# Audio.net
KiCad netlist of a schematic drawn in Altium Designer
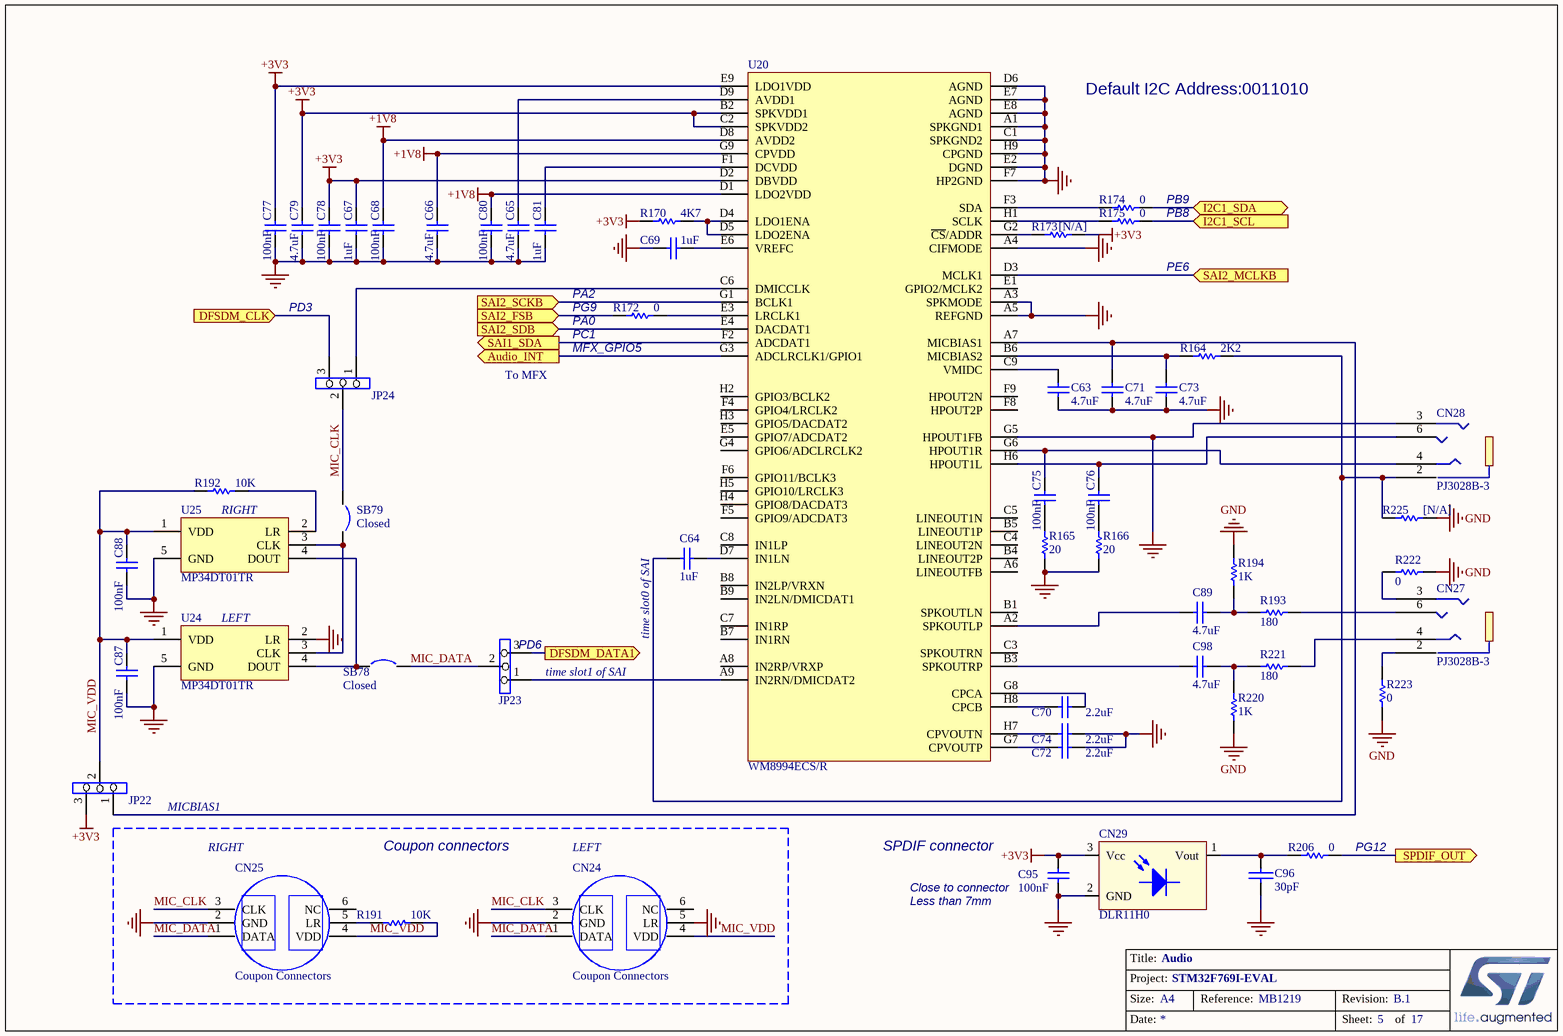
[diagram p0: Audio.SchDoc]

(export (version "E")
  (design (tool "Eeschema 10.0.6"))
  (components
    (comp (ref "C63")
      (value "4.7uF")
      (footprint "0603C")
      (description "Capacitor")
      (fields (field (name "PUBLISHER") "Altium Limited"))
      (libsource (lib "Miscellaneous Devices") (part "Cap"))
    )
    (comp (ref "C64")
      (value "1uF")
      (footprint "0603C")
      (description "Capacitor")
      (fields (field (name "PUBLISHER") "Altium Limited"))
      (libsource (lib "Miscellaneous Devices") (part "CAP"))
    )
    (comp (ref "C65")
      (value "4.7uF")
      (footprint "0603C")
      (description "Capacitor")
      (fields (field (name "PUBLISHER") "Altium Limited"))
      (libsource (lib "Miscellaneous Devices") (part "Cap"))
    )
    (comp (ref "C66")
      (value "4.7uF")
      (footprint "0603C")
      (description "Capacitor")
      (fields (field (name "PUBLISHER") "Altium Limited"))
      (libsource (lib "Miscellaneous Devices") (part "Cap"))
    )
    (comp (ref "C67")
      (value "1uF")
      (footprint "0603C")
      (description "Capacitor")
      (fields (field (name "PUBLISHER") "Altium Limited"))
      (libsource (lib "Miscellaneous Devices") (part "CAP"))
    )
    (comp (ref "C68")
      (value "100nF")
      (footprint "0603C")
      (description "Capacitor")
      (fields (field (name "PUBLISHER") "Altium Limited"))
      (libsource (lib "Miscellaneous Devices") (part "Cap"))
    )
    (comp (ref "C69")
      (value "1uF")
      (footprint "0603C")
      (description "Capacitor")
      (fields (field (name "PUBLISHER") "Altium Limited"))
      (libsource (lib "Miscellaneous Devices") (part "CAP"))
    )
    (comp (ref "C70")
      (value "2.2uF")
      (footprint "0603C")
      (description "Capacitor")
      (fields (field (name "PUBLISHER") "Altium Limited"))
      (libsource (lib "Miscellaneous Devices") (part "CAP"))
    )
    (comp (ref "C71")
      (value "4.7uF")
      (footprint "0603C")
      (description "Capacitor")
      (fields (field (name "PUBLISHER") "Altium Limited"))
      (libsource (lib "Miscellaneous Devices") (part "Cap"))
    )
    (comp (ref "C72")
      (value "2.2uF")
      (footprint "0603C")
      (description "Capacitor")
      (fields (field (name "PUBLISHER") "Altium Limited"))
      (libsource (lib "Miscellaneous Devices") (part "CAP"))
    )
    (comp (ref "C73")
      (value "4.7uF")
      (footprint "0603C")
      (description "Capacitor")
      (fields (field (name "PUBLISHER") "Altium Limited"))
      (libsource (lib "Miscellaneous Devices") (part "Cap"))
    )
    (comp (ref "C74")
      (value "2.2uF")
      (footprint "0603C")
      (description "Capacitor")
      (fields (field (name "PUBLISHER") "Altium Limited"))
      (libsource (lib "Miscellaneous Devices") (part "CAP"))
    )
    (comp (ref "C75")
      (value "100nF")
      (footprint "0603C")
      (description "Capacitor")
      (fields (field (name "PUBLISHER") "Altium Limited"))
      (libsource (lib "Miscellaneous Devices") (part "Cap"))
    )
    (comp (ref "C76")
      (value "100nF")
      (footprint "0603C")
      (description "Capacitor")
      (fields (field (name "PUBLISHER") "Altium Limited"))
      (libsource (lib "Miscellaneous Devices") (part "Cap"))
    )
    (comp (ref "C77")
      (value "100nF")
      (footprint "0603C")
      (description "Capacitor")
      (fields (field (name "PUBLISHER") "Altium Limited"))
      (libsource (lib "Miscellaneous Devices") (part "Cap"))
    )
    (comp (ref "C78")
      (value "100nF")
      (footprint "0603C")
      (description "Capacitor")
      (fields (field (name "PUBLISHER") "Altium Limited"))
      (libsource (lib "Miscellaneous Devices") (part "Cap"))
    )
    (comp (ref "C79")
      (value "4.7uF")
      (footprint "0603C")
      (description "Capacitor")
      (fields (field (name "PUBLISHER") "Altium Limited"))
      (libsource (lib "Miscellaneous Devices") (part "Cap"))
    )
    (comp (ref "C80")
      (value "100nF")
      (footprint "0603C")
      (description "Capacitor")
      (fields (field (name "PUBLISHER") "Altium Limited"))
      (libsource (lib "Miscellaneous Devices") (part "Cap"))
    )
    (comp (ref "C81")
      (value "1uF")
      (footprint "0603C")
      (description "Capacitor")
      (fields (field (name "PUBLISHER") "Altium Limited"))
      (libsource (lib "Miscellaneous Devices") (part "CAP"))
    )
    (comp (ref "C87")
      (value "100nF")
      (footprint "0603C")
      (description "Capacitor")
      (fields (field (name "PUBLISHER") "Altium Limited"))
      (libsource (lib "Miscellaneous Devices") (part "Cap"))
    )
    (comp (ref "C88")
      (value "100nF")
      (footprint "0603C")
      (description "Capacitor")
      (fields (field (name "PUBLISHER") "Altium Limited"))
      (libsource (lib "Miscellaneous Devices") (part "Cap"))
    )
    (comp (ref "C89")
      (value "4.7uF")
      (footprint "0603C")
      (description "Capacitor")
      (fields (field (name "PUBLISHER") "Altium Limited"))
      (libsource (lib "Miscellaneous Devices") (part "Cap"))
    )
    (comp (ref "C95")
      (value "100nF")
      (footprint "0603C")
      (description "Capacitor")
      (fields (field (name "PUBLISHER") "Altium Limited"))
      (libsource (lib "Miscellaneous Devices") (part "Cap"))
    )
    (comp (ref "C96")
      (value "30pF")
      (footprint "0603C")
      (description "Capacitor")
      (libsource (lib "*") (part "CAP"))
    )
    (comp (ref "C98")
      (value "4.7uF")
      (footprint "0603C")
      (description "Capacitor")
      (fields (field (name "PUBLISHER") "Altium Limited"))
      (libsource (lib "Miscellaneous Devices") (part "Cap"))
    )
    (comp (ref "CN24")
      (value "Coupon Connectors")
      (footprint "Coupon")
      (description "Header, 3-Pin, Single row")
      (fields (field (name "PUBLISHER") "Altium Limited"))
      (libsource (lib "MB1167") (part "Coupon Connectors"))
    )
    (comp (ref "CN25")
      (value "Coupon Connectors")
      (footprint "Coupon")
      (description "Header, 3-Pin, Single row")
      (fields (field (name "PUBLISHER") "Altium Limited"))
      (libsource (lib "MB1167") (part "Coupon Connectors"))
    )
    (comp (ref "CN27") (value "PJ3028B-3") (footprint "PJ3028B") (libsource (lib "MB786") (part "PJ3028B-3")))
    (comp (ref "CN28") (value "PJ3028B-3") (footprint "PJ3028B") (libsource (lib "MB786") (part "PJ3028B-3")))
    (comp (ref "CN29")
      (value "DLR11H0")
      (footprint "CONN_DLR11H0")
      (libsource (lib "MB1167_1") (part "OPTO"))
    )
    (comp (ref "JP22") (value "~") (footprint "SIP3") (libsource (lib "STR910_SCHLIB") (part "Jumper3")))
    (comp (ref "JP23") (value "~") (footprint "SIP3") (libsource (lib "STR910_SCHLIB") (part "Jumper3")))
    (comp (ref "JP24") (value "~") (footprint "SIP3") (libsource (lib "STR910_SCHLIB") (part "Jumper3")))
    (comp (ref "R164")
      (value "2K2")
      (footprint "0603R")
      (description "Resistor")
      (fields (field (name "PUBLISHER") "Altium Limited"))
      (libsource (lib "Miscellaneous Devices") (part "Res1"))
    )
    (comp (ref "R165")
      (value "20")
      (footprint "0603R")
      (description "Resistor")
      (fields (field (name "PUBLISHER") "Altium Limited"))
      (libsource (lib "Miscellaneous Devices") (part "Res1"))
    )
    (comp (ref "R166")
      (value "20")
      (footprint "0603R")
      (description "Resistor")
      (fields (field (name "PUBLISHER") "Altium Limited"))
      (libsource (lib "Miscellaneous Devices") (part "Res1"))
    )
    (comp (ref "R170")
      (value "4K7")
      (footprint "0603R")
      (description "Resistor")
      (fields (field (name "PUBLISHER") "Altium Limited"))
      (libsource (lib "Miscellaneous Devices") (part "Res1"))
    )
    (comp (ref "R172")
      (value "0")
      (footprint "0603R")
      (description "Resistor")
      (fields (field (name "PUBLISHER") "Altium Limited"))
      (libsource (lib "Miscellaneous Devices") (part "Res1"))
    )
    (comp (ref "R173")
      (value "[N/A]")
      (footprint "0603R")
      (description "Resistor")
      (fields (field (name "PUBLISHER") "Altium Limited"))
      (libsource (lib "Miscellaneous Devices") (part "Res1"))
    )
    (comp (ref "R174")
      (value "0")
      (footprint "0603R")
      (description "Resistor")
      (fields (field (name "PUBLISHER") "Altium Limited"))
      (libsource (lib "Miscellaneous Devices") (part "Res1"))
    )
    (comp (ref "R175")
      (value "0")
      (footprint "0603R")
      (description "Resistor")
      (fields (field (name "PUBLISHER") "Altium Limited"))
      (libsource (lib "Miscellaneous Devices") (part "Res1"))
    )
    (comp (ref "R191")
      (value "10K")
      (footprint "0603R")
      (description "Resistor")
      (fields (field (name "PUBLISHER") "Altium Limited"))
      (libsource (lib "Miscellaneous Devices") (part "Res1"))
    )
    (comp (ref "R192")
      (value "10K")
      (footprint "0603R")
      (description "Resistor")
      (fields (field (name "PUBLISHER") "Altium Limited"))
      (libsource (lib "Miscellaneous Devices") (part "Res1"))
    )
    (comp (ref "R193")
      (value "180")
      (footprint "0402R")
      (description "Resistor")
      (fields (field (name "PUBLISHER") "Altium Limited"))
      (libsource (lib "Miscellaneous Devices") (part "Res1"))
    )
    (comp (ref "R194")
      (value "1K")
      (footprint "0402R")
      (description "Resistor")
      (fields (field (name "PUBLISHER") "Altium Limited"))
      (libsource (lib "Miscellaneous Devices") (part "Res1"))
    )
    (comp (ref "R206")
      (value "0")
      (footprint "0603R")
      (description "Resistor")
      (fields (field (name "PUBLISHER") "Altium Limited"))
      (libsource (lib "Miscellaneous Devices") (part "Res1"))
    )
    (comp (ref "R220")
      (value "1K")
      (footprint "0402R")
      (description "Resistor")
      (fields (field (name "PUBLISHER") "Altium Limited"))
      (libsource (lib "Miscellaneous Devices") (part "Res1"))
    )
    (comp (ref "R221")
      (value "180")
      (footprint "0402R")
      (description "Resistor")
      (fields (field (name "PUBLISHER") "Altium Limited"))
      (libsource (lib "Miscellaneous Devices") (part "Res1"))
    )
    (comp (ref "R222")
      (value "0")
      (footprint "0603R")
      (description "Resistor")
      (fields (field (name "PUBLISHER") "Altium Limited"))
      (libsource (lib "Miscellaneous Devices") (part "Res1"))
    )
    (comp (ref "R223")
      (value "0")
      (footprint "0603R")
      (description "Resistor")
      (fields (field (name "PUBLISHER") "Altium Limited"))
      (libsource (lib "Miscellaneous Devices") (part "Res1"))
    )
    (comp (ref "R225")
      (value "[N/A]")
      (footprint "0603R")
      (description "Resistor")
      (fields (field (name "PUBLISHER") "Altium Limited"))
      (libsource (lib "Miscellaneous Devices") (part "Res1"))
    )
    (comp (ref "SB78")
      (value "Closed")
      (footprint "SB_0603")
      (description "Circuit Breaker")
      (fields (field (name "PUBLISHER") "Altium Limited"))
      (libsource (lib "MB1167") (part "Circuit Breaker_close"))
    )
    (comp (ref "SB79")
      (value "Closed")
      (footprint "SB_0603")
      (description "Circuit Breaker")
      (fields (field (name "PUBLISHER") "Altium Limited"))
      (libsource (lib "MB1167") (part "Circuit Breaker_close"))
    )
    (comp (ref "U20")
      (value "WM8994ECS/R")
      (footprint "BGA72_0R5_4R5X4")
      (libsource (lib "mb1045") (part "WM8994ECS/R"))
    )
    (comp (ref "U24")
      (value "MP34DT01TR")
      (footprint "MP34DT01TR")
      (description "MEMS audio sensor")
      (fields (field (name "PUBLISHER") "Altium Limited"))
      (libsource (lib "mb1045") (part "MP34DT01TR"))
    )
    (comp (ref "U25")
      (value "MP34DT01TR")
      (footprint "MP34DT01TR")
      (description "MEMS audio sensor")
      (fields (field (name "PUBLISHER") "Altium Limited"))
      (libsource (lib "mb1045") (part "MP34DT01TR"))
    )
  )
  (nets
    (net (code "1") (name "+1V8") (class "Default")
      (node (ref "C66") (pin "1") (pinfunction "1_1") (pintype "passive"))
      (node (ref "C68") (pin "1") (pinfunction "1_1") (pintype "passive"))
      (node (ref "C80") (pin "1") (pinfunction "1_1") (pintype "passive"))
      (node (ref "U20") (pin "D1") (pinfunction "LDO2VDD_D1") (pintype "passive"))
      (node (ref "U20") (pin "D8") (pinfunction "AVDD2_D8") (pintype "passive"))
      (node (ref "U20") (pin "G9") (pinfunction "CPVDD_G9") (pintype "passive"))
    )
    (net (code "2") (name "+3V3") (class "Default")
      (node (ref "C67") (pin "1") (pinfunction "1_1") (pintype "passive"))
      (node (ref "C77") (pin "1") (pinfunction "1_1") (pintype "passive"))
      (node (ref "C78") (pin "1") (pinfunction "1_1") (pintype "passive"))
      (node (ref "C79") (pin "1") (pinfunction "1_1") (pintype "passive"))
      (node (ref "C95") (pin "2") (pinfunction "2_2") (pintype "passive"))
      (node (ref "CN29") (pin "3") (pinfunction "Vcc_3") (pintype "passive"))
      (node (ref "JP22") (pin "3") (pintype "passive"))
      (node (ref "R170") (pin "2") (pinfunction "2_2") (pintype "passive"))
      (node (ref "R173") (pin "1") (pinfunction "1_1") (pintype "passive"))
      (node (ref "U20") (pin "B2") (pinfunction "SPKVDD1_B2") (pintype "passive"))
      (node (ref "U20") (pin "C2") (pinfunction "SPKVDD2_C2") (pintype "passive"))
      (node (ref "U20") (pin "D2") (pinfunction "DBVDD_D2") (pintype "passive"))
      (node (ref "U20") (pin "E9") (pinfunction "LDO1VDD_E9") (pintype "passive"))
    )
    (net (code "3") (name "/Audio_INT") (class "Default")
      (node (ref "U20") (pin "G3") (pinfunction "ADCLRCLK1/GPIO1_G3") (pintype "passive"))
    )
    (net (code "4") (name "/DFSDM_CLK") (class "Default") (node (ref "JP24") (pin "3") (pintype "passive")))
    (net (code "5") (name "/DFSDM_DATA1") (class "Default") (node (ref "JP23") (pin "3") (pintype "passive")))
    (net (code "6") (name "/I2C1_SCL") (class "Default")
      (node (ref "R175") (pin "1") (pinfunction "1_1") (pintype "passive"))
    )
    (net (code "7") (name "/I2C1_SDA") (class "Default")
      (node (ref "R174") (pin "1") (pinfunction "1_1") (pintype "passive"))
    )
    (net (code "8") (name "/MIC_CLK") (class "Default")
      (node (ref "CN24") (pin "3") (pinfunction "CLK_3") (pintype "passive"))
      (node (ref "CN25") (pin "3") (pinfunction "CLK_3") (pintype "passive"))
      (node (ref "JP24") (pin "2") (pintype "passive"))
      (node (ref "SB79") (pin "1") (pinfunction "1_1") (pintype "passive"))
    )
    (net (code "9") (name "/MIC_DATA") (class "Default")
      (node (ref "CN24") (pin "1") (pinfunction "DATA_1") (pintype "passive"))
      (node (ref "CN25") (pin "1") (pinfunction "DATA_1") (pintype "passive"))
      (node (ref "JP23") (pin "2") (pintype "passive"))
      (node (ref "SB78") (pin "2") (pinfunction "2_2") (pintype "passive"))
    )
    (net (code "10") (name "/MIC_VDD") (class "Default")
      (node (ref "C87") (pin "1") (pinfunction "1_1") (pintype "passive"))
      (node (ref "C88") (pin "1") (pinfunction "1_1") (pintype "passive"))
      (node (ref "CN24") (pin "4") (pinfunction "VDD_4") (pintype "passive"))
      (node (ref "CN25") (pin "4") (pinfunction "VDD_4") (pintype "passive"))
      (node (ref "JP22") (pin "2") (pintype "passive"))
      (node (ref "R191") (pin "2") (pinfunction "2_2") (pintype "passive"))
      (node (ref "R192") (pin "2") (pinfunction "2_2") (pintype "passive"))
      (node (ref "U24") (pin "1") (pinfunction "VDD_1") (pintype "passive"))
      (node (ref "U25") (pin "1") (pinfunction "VDD_1") (pintype "passive"))
    )
    (net (code "11") (name "/SAI1_SDA") (class "Default")
      (node (ref "U20") (pin "F2") (pinfunction "ADCDAT1_F2") (pintype "passive"))
    )
    (net (code "12") (name "/SAI2_FSB") (class "Default")
      (node (ref "R172") (pin "2") (pinfunction "2_2") (pintype "passive"))
    )
    (net (code "13") (name "/SAI2_MCLKB") (class "Default")
      (node (ref "U20") (pin "D3") (pinfunction "MCLK1_D3") (pintype "passive"))
    )
    (net (code "14") (name "/SAI2_SCKB") (class "Default")
      (node (ref "U20") (pin "G1") (pinfunction "BCLK1_G1") (pintype "passive"))
    )
    (net (code "15") (name "/SAI2_SDB") (class "Default")
      (node (ref "U20") (pin "E4") (pinfunction "DACDAT1_E4") (pintype "passive"))
    )
    (net (code "16") (name "/SPDIF_OUT") (class "Default")
      (node (ref "R206") (pin "1") (pinfunction "1_1") (pintype "passive"))
    )
    (net (code "17") (name "GND") (class "Default")
      (node (ref "C63") (pin "1") (pinfunction "1_1") (pintype "passive"))
      (node (ref "C65") (pin "2") (pinfunction "2_2") (pintype "passive"))
      (node (ref "C66") (pin "2") (pinfunction "2_2") (pintype "passive"))
      (node (ref "C67") (pin "2") (pinfunction "2_2") (pintype "passive"))
      (node (ref "C68") (pin "2") (pinfunction "2_2") (pintype "passive"))
      (node (ref "C69") (pin "2") (pinfunction "2_2") (pintype "passive"))
      (node (ref "C71") (pin "1") (pinfunction "1_1") (pintype "passive"))
      (node (ref "C72") (pin "2") (pinfunction "2_2") (pintype "passive"))
      (node (ref "C73") (pin "1") (pinfunction "1_1") (pintype "passive"))
      (node (ref "C74") (pin "2") (pinfunction "2_2") (pintype "passive"))
      (node (ref "C77") (pin "2") (pinfunction "2_2") (pintype "passive"))
      (node (ref "C78") (pin "2") (pinfunction "2_2") (pintype "passive"))
      (node (ref "C79") (pin "2") (pinfunction "2_2") (pintype "passive"))
      (node (ref "C80") (pin "2") (pinfunction "2_2") (pintype "passive"))
      (node (ref "C81") (pin "2") (pinfunction "2_2") (pintype "passive"))
      (node (ref "C87") (pin "2") (pinfunction "2_2") (pintype "passive"))
      (node (ref "C88") (pin "2") (pinfunction "2_2") (pintype "passive"))
      (node (ref "C95") (pin "1") (pinfunction "1_1") (pintype "passive"))
      (node (ref "C96") (pin "2") (pinfunction "2_2") (pintype "passive"))
      (node (ref "CN24") (pin "2") (pinfunction "GND_2") (pintype "passive"))
      (node (ref "CN24") (pin "5") (pinfunction "LR_5") (pintype "passive"))
      (node (ref "CN25") (pin "2") (pinfunction "GND_2") (pintype "passive"))
      (node (ref "CN28") (pin "3") (pintype "passive"))
      (node (ref "CN29") (pin "2") (pinfunction "GND_2") (pintype "passive"))
      (node (ref "R165") (pin "2") (pinfunction "2_2") (pintype "passive"))
      (node (ref "R166") (pin "2") (pinfunction "2_2") (pintype "passive"))
      (node (ref "R194") (pin "2") (pinfunction "2_2") (pintype "passive"))
      (node (ref "R220") (pin "1") (pinfunction "1_1") (pintype "passive"))
      (node (ref "R222") (pin "2") (pinfunction "2_2") (pintype "passive"))
      (node (ref "R223") (pin "2") (pinfunction "2_2") (pintype "passive"))
      (node (ref "R225") (pin "1") (pinfunction "1_1") (pintype "passive"))
      (node (ref "U20") (pin "A1") (pinfunction "SPKGND1_A1") (pintype "passive"))
      (node (ref "U20") (pin "A3") (pinfunction "SPKMODE_A3") (pintype "passive"))
      (node (ref "U20") (pin "A4") (pinfunction "CIFMODE_A4") (pintype "passive"))
      (node (ref "U20") (pin "A5") (pinfunction "REFGND_A5") (pintype "passive"))
      (node (ref "U20") (pin "C1") (pinfunction "SPKGND2_C1") (pintype "passive"))
      (node (ref "U20") (pin "D6") (pinfunction "AGND_D6") (pintype "passive"))
      (node (ref "U20") (pin "E2") (pinfunction "DGND_E2") (pintype "passive"))
      (node (ref "U20") (pin "E7") (pinfunction "AGND_E7") (pintype "passive"))
      (node (ref "U20") (pin "E8") (pinfunction "AGND_E8") (pintype "passive"))
      (node (ref "U20") (pin "F7") (pinfunction "HP2GND_F7") (pintype "passive"))
      (node (ref "U20") (pin "G5") (pinfunction "HPOUT1FB_G5") (pintype "passive"))
      (node (ref "U20") (pin "H9") (pinfunction "CPGND_H9") (pintype "passive"))
      (node (ref "U24") (pin "2") (pinfunction "LR_2") (pintype "passive"))
      (node (ref "U24") (pin "5") (pinfunction "GND_5") (pintype "passive"))
      (node (ref "U25") (pin "5") (pinfunction "GND_5") (pintype "passive"))
    )
    (net (code "18") (name "Net-(C64-Pad2)") (class "Default")
      (node (ref "C64") (pin "2") (pinfunction "2_2") (pintype "passive"))
      (node (ref "CN28") (pin "2") (pintype "passive"))
      (node (ref "R164") (pin "1") (pinfunction "1_1") (pintype "passive"))
      (node (ref "R225") (pin "2") (pinfunction "2_2") (pintype "passive"))
    )
    (net (code "19") (name "Net-(C75-Pad2)") (class "Default")
      (node (ref "C75") (pin "2") (pinfunction "2_2") (pintype "passive"))
      (node (ref "R165") (pin "1") (pinfunction "1_1") (pintype "passive"))
    )
    (net (code "20") (name "Net-(C76-Pad2)") (class "Default")
      (node (ref "C76") (pin "2") (pinfunction "2_2") (pintype "passive"))
      (node (ref "R166") (pin "1") (pinfunction "1_1") (pintype "passive"))
    )
    (net (code "21") (name "Net-(C89-Pad1)") (class "Default")
      (node (ref "C89") (pin "1") (pinfunction "1_1") (pintype "passive"))
      (node (ref "R193") (pin "1") (pinfunction "1_1") (pintype "passive"))
      (node (ref "R194") (pin "1") (pinfunction "1_1") (pintype "passive"))
    )
    (net (code "22") (name "Net-(C98-Pad1)") (class "Default")
      (node (ref "C98") (pin "1") (pinfunction "1_1") (pintype "passive"))
      (node (ref "R220") (pin "2") (pinfunction "2_2") (pintype "passive"))
      (node (ref "R221") (pin "2") (pinfunction "2_2") (pintype "passive"))
    )
    (net (code "23") (name "Net-(CN25-LR)") (class "Default")
      (node (ref "CN25") (pin "5") (pinfunction "LR_5") (pintype "passive"))
      (node (ref "R191") (pin "1") (pinfunction "1_1") (pintype "passive"))
    )
    (net (code "24") (name "Net-(CN27-Pad2)") (class "Default")
      (node (ref "CN27") (pin "2") (pintype "passive"))
      (node (ref "R223") (pin "1") (pinfunction "1_1") (pintype "passive"))
    )
    (net (code "25") (name "Net-(CN27-Pad3)") (class "Default")
      (node (ref "CN27") (pin "3") (pintype "passive"))
      (node (ref "R222") (pin "1") (pinfunction "1_1") (pintype "passive"))
    )
    (net (code "26") (name "Net-(CN27-Pad4)") (class "Default")
      (node (ref "CN27") (pin "4") (pintype "passive"))
      (node (ref "R221") (pin "1") (pinfunction "1_1") (pintype "passive"))
    )
    (net (code "27") (name "Net-(CN27-Pad6)") (class "Default")
      (node (ref "CN27") (pin "6") (pintype "passive"))
      (node (ref "R193") (pin "2") (pinfunction "2_2") (pintype "passive"))
    )
    (net (code "28") (name "Net-(CN29-Vout)") (class "Default")
      (node (ref "C96") (pin "1") (pinfunction "1_1") (pintype "passive"))
      (node (ref "CN29") (pin "1") (pinfunction "Vout_1") (pintype "passive"))
      (node (ref "R206") (pin "2") (pinfunction "2_2") (pintype "passive"))
    )
    (net (code "29") (name "Net-(U20-AVDD1)") (class "Default")
      (node (ref "C65") (pin "1") (pinfunction "1_1") (pintype "passive"))
      (node (ref "U20") (pin "D9") (pinfunction "AVDD1_D9") (pintype "passive"))
    )
    (net (code "30") (name "Net-(U20-CPCA)") (class "Default")
      (node (ref "C70") (pin "2") (pinfunction "2_2") (pintype "passive"))
      (node (ref "U20") (pin "G8") (pinfunction "CPCA_G8") (pintype "passive"))
    )
    (net (code "31") (name "Net-(U20-CPCB)") (class "Default")
      (node (ref "C70") (pin "1") (pinfunction "1_1") (pintype "passive"))
      (node (ref "U20") (pin "H8") (pinfunction "CPCB_H8") (pintype "passive"))
    )
    (net (code "32") (name "Net-(U20-CPVOUTN)") (class "Default")
      (node (ref "C74") (pin "1") (pinfunction "1_1") (pintype "passive"))
      (node (ref "U20") (pin "H7") (pinfunction "CPVOUTN_H7") (pintype "passive"))
    )
    (net (code "33") (name "Net-(U20-CPVOUTP)") (class "Default")
      (node (ref "C72") (pin "1") (pinfunction "1_1") (pintype "passive"))
      (node (ref "U20") (pin "G7") (pinfunction "CPVOUTP_G7") (pintype "passive"))
    )
    (net (code "34") (name "Net-(U20-DCVDD)") (class "Default")
      (node (ref "C81") (pin "1") (pinfunction "1_1") (pintype "passive"))
      (node (ref "U20") (pin "F1") (pinfunction "DCVDD_F1") (pintype "passive"))
    )
    (net (code "35") (name "Net-(U20-DMICCLK)") (class "Default")
      (node (ref "JP24") (pin "1") (pintype "passive"))
      (node (ref "U20") (pin "C6") (pinfunction "DMICCLK_C6") (pintype "passive"))
    )
    (net (code "36") (name "Net-(U20-HPOUT1L)") (class "Default")
      (node (ref "C76") (pin "1") (pinfunction "1_1") (pintype "passive"))
      (node (ref "CN28") (pin "6") (pintype "passive"))
      (node (ref "U20") (pin "H6") (pinfunction "HPOUT1L_H6") (pintype "passive"))
    )
    (net (code "37") (name "Net-(U20-HPOUT1R)") (class "Default")
      (node (ref "C75") (pin "1") (pinfunction "1_1") (pintype "passive"))
      (node (ref "CN28") (pin "4") (pintype "passive"))
      (node (ref "U20") (pin "G6") (pinfunction "HPOUT1R_G6") (pintype "passive"))
    )
    (net (code "38") (name "Net-(U20-IN1LN)") (class "Default")
      (node (ref "C64") (pin "1") (pinfunction "1_1") (pintype "passive"))
      (node (ref "U20") (pin "D7") (pinfunction "IN1LN_D7") (pintype "passive"))
    )
    (net (code "39") (name "Net-(U20-IN2RN{slash}DMICDAT2)") (class "Default")
      (node (ref "JP23") (pin "1") (pintype "passive"))
      (node (ref "U20") (pin "A9") (pinfunction "IN2RN/DMICDAT2_A9") (pintype "passive"))
    )
    (net (code "40") (name "Net-(U20-LDO1ENA)") (class "Default")
      (node (ref "R170") (pin "1") (pinfunction "1_1") (pintype "passive"))
      (node (ref "U20") (pin "D4") (pinfunction "LDO1ENA_D4") (pintype "passive"))
      (node (ref "U20") (pin "D5") (pinfunction "LDO2ENA_D5") (pintype "passive"))
    )
    (net (code "41") (name "Net-(U20-LRCLK1)") (class "Default")
      (node (ref "R172") (pin "1") (pinfunction "1_1") (pintype "passive"))
      (node (ref "U20") (pin "E3") (pinfunction "LRCLK1_E3") (pintype "passive"))
    )
    (net (code "42") (name "Net-(U20-MICBIAS1)") (class "Default")
      (node (ref "C71") (pin "2") (pinfunction "2_2") (pintype "passive"))
      (node (ref "JP22") (pin "1") (pintype "passive"))
      (node (ref "U20") (pin "A7") (pinfunction "MICBIAS1_A7") (pintype "passive"))
    )
    (net (code "43") (name "Net-(U20-MICBIAS2)") (class "Default")
      (node (ref "C73") (pin "2") (pinfunction "2_2") (pintype "passive"))
      (node (ref "R164") (pin "2") (pinfunction "2_2") (pintype "passive"))
      (node (ref "U20") (pin "B6") (pinfunction "MICBIAS2_B6") (pintype "passive"))
    )
    (net (code "44") (name "Net-(U20-SCLK)") (class "Default")
      (node (ref "R175") (pin "2") (pinfunction "2_2") (pintype "passive"))
      (node (ref "U20") (pin "H1") (pinfunction "SCLK_H1") (pintype "passive"))
    )
    (net (code "45") (name "Net-(U20-SDA)") (class "Default")
      (node (ref "R174") (pin "2") (pinfunction "2_2") (pintype "passive"))
      (node (ref "U20") (pin "F3") (pinfunction "SDA_F3") (pintype "passive"))
    )
    (net (code "46") (name "Net-(U20-SPKOUTLP)") (class "Default")
      (node (ref "C89") (pin "2") (pinfunction "2_2") (pintype "passive"))
      (node (ref "U20") (pin "A2") (pinfunction "SPKOUTLP_A2") (pintype "passive"))
    )
    (net (code "47") (name "Net-(U20-SPKOUTRP)") (class "Default")
      (node (ref "C98") (pin "2") (pinfunction "2_2") (pintype "passive"))
      (node (ref "U20") (pin "B3") (pinfunction "SPKOUTRP_B3") (pintype "passive"))
    )
    (net (code "48") (name "Net-(U20-VMIDC)") (class "Default")
      (node (ref "C63") (pin "2") (pinfunction "2_2") (pintype "passive"))
      (node (ref "U20") (pin "C9") (pinfunction "VMIDC_C9") (pintype "passive"))
    )
    (net (code "49") (name "Net-(U20-VREFC)") (class "Default")
      (node (ref "C69") (pin "1") (pinfunction "1_1") (pintype "passive"))
      (node (ref "U20") (pin "E6") (pinfunction "VREFC_E6") (pintype "passive"))
    )
    (net (code "50") (name "Net-(U20-~{CS}{slash}ADDR)") (class "Default")
      (node (ref "R173") (pin "2") (pinfunction "2_2") (pintype "passive"))
      (node (ref "U20") (pin "G2") (pinfunction "~{CS}/ADDR_G2") (pintype "passive"))
    )
    (net (code "51") (name "Net-(U24-CLK)") (class "Default")
      (node (ref "SB79") (pin "2") (pinfunction "2_2") (pintype "passive"))
      (node (ref "U24") (pin "3") (pinfunction "CLK_3") (pintype "passive"))
      (node (ref "U25") (pin "3") (pinfunction "CLK_3") (pintype "passive"))
    )
    (net (code "52") (name "Net-(U24-DOUT)") (class "Default")
      (node (ref "SB78") (pin "1") (pinfunction "1_1") (pintype "passive"))
      (node (ref "U24") (pin "4") (pinfunction "DOUT_4") (pintype "passive"))
      (node (ref "U25") (pin "4") (pinfunction "DOUT_4") (pintype "passive"))
    )
    (net (code "53") (name "Net-(U25-LR)") (class "Default")
      (node (ref "R192") (pin "1") (pinfunction "1_1") (pintype "passive"))
      (node (ref "U25") (pin "2") (pinfunction "LR_2") (pintype "passive"))
    )
    (net (code "54") (name "unconnected-(CN24-NC-Pad6)") (class "Default")
      (node (ref "CN24") (pin "6") (pinfunction "NC_6") (pintype "passive"))
    )
    (net (code "55") (name "unconnected-(CN25-NC-Pad6)") (class "Default")
      (node (ref "CN25") (pin "6") (pinfunction "NC_6") (pintype "passive"))
    )
    (net (code "56") (name "unconnected-(U20-GPIO2{slash}MCLK2-PadE1)") (class "Default")
      (node (ref "U20") (pin "E1") (pinfunction "GPIO2/MCLK2_E1") (pintype "passive"))
    )
    (net (code "57") (name "unconnected-(U20-GPIO3{slash}BCLK2-PadH2)") (class "Default")
      (node (ref "U20") (pin "H2") (pinfunction "GPIO3/BCLK2_H2") (pintype "passive"))
    )
    (net (code "58") (name "unconnected-(U20-GPIO4{slash}LRCLK2-PadF4)") (class "Default")
      (node (ref "U20") (pin "F4") (pinfunction "GPIO4/LRCLK2_F4") (pintype "passive"))
    )
    (net (code "59") (name "unconnected-(U20-GPIO5{slash}DACDAT2-PadH3)") (class "Default")
      (node (ref "U20") (pin "H3") (pinfunction "GPIO5/DACDAT2_H3") (pintype "passive"))
    )
    (net (code "60") (name "unconnected-(U20-GPIO6{slash}ADCLRCLK2-PadG4)") (class "Default")
      (node (ref "U20") (pin "G4") (pinfunction "GPIO6/ADCLRCLK2_G4") (pintype "passive"))
    )
    (net (code "61") (name "unconnected-(U20-GPIO7{slash}ADCDAT2-PadE5)") (class "Default")
      (node (ref "U20") (pin "E5") (pinfunction "GPIO7/ADCDAT2_E5") (pintype "passive"))
    )
    (net (code "62") (name "unconnected-(U20-GPIO8{slash}DACDAT3-PadH4)") (class "Default")
      (node (ref "U20") (pin "H4") (pinfunction "GPIO8/DACDAT3_H4") (pintype "passive"))
    )
    (net (code "63") (name "unconnected-(U20-GPIO9{slash}ADCDAT3-PadF5)") (class "Default")
      (node (ref "U20") (pin "F5") (pinfunction "GPIO9/ADCDAT3_F5") (pintype "passive"))
    )
    (net (code "64") (name "unconnected-(U20-GPIO10{slash}LRCLK3-PadH5)") (class "Default")
      (node (ref "U20") (pin "H5") (pinfunction "GPIO10/LRCLK3_H5") (pintype "passive"))
    )
    (net (code "65") (name "unconnected-(U20-GPIO11{slash}BCLK3-PadF6)") (class "Default")
      (node (ref "U20") (pin "F6") (pinfunction "GPIO11/BCLK3_F6") (pintype "passive"))
    )
    (net (code "66") (name "unconnected-(U20-HPOUT2N-PadF9)") (class "Default")
      (node (ref "U20") (pin "F9") (pinfunction "HPOUT2N_F9") (pintype "passive"))
    )
    (net (code "67") (name "unconnected-(U20-HPOUT2P-PadF8)") (class "Default")
      (node (ref "U20") (pin "F8") (pinfunction "HPOUT2P_F8") (pintype "passive"))
    )
    (net (code "68") (name "unconnected-(U20-IN1LP-PadC8)") (class "Default")
      (node (ref "U20") (pin "C8") (pinfunction "IN1LP_C8") (pintype "passive"))
    )
    (net (code "69") (name "unconnected-(U20-IN1RN-PadB7)") (class "Default")
      (node (ref "U20") (pin "B7") (pinfunction "IN1RN_B7") (pintype "passive"))
    )
    (net (code "70") (name "unconnected-(U20-IN1RP-PadC7)") (class "Default")
      (node (ref "U20") (pin "C7") (pinfunction "IN1RP_C7") (pintype "passive"))
    )
    (net (code "71") (name "unconnected-(U20-IN2LN{slash}DMICDAT1-PadB9)") (class "Default")
      (node (ref "U20") (pin "B9") (pinfunction "IN2LN/DMICDAT1_B9") (pintype "passive"))
    )
    (net (code "72") (name "unconnected-(U20-IN2LP{slash}VRXN-PadB8)") (class "Default")
      (node (ref "U20") (pin "B8") (pinfunction "IN2LP/VRXN_B8") (pintype "passive"))
    )
    (net (code "73") (name "unconnected-(U20-IN2RP{slash}VRXP-PadA8)") (class "Default")
      (node (ref "U20") (pin "A8") (pinfunction "IN2RP/VRXP_A8") (pintype "passive"))
    )
    (net (code "74") (name "unconnected-(U20-LINEOUT1N-PadC5)") (class "Default")
      (node (ref "U20") (pin "C5") (pinfunction "LINEOUT1N_C5") (pintype "passive"))
    )
    (net (code "75") (name "unconnected-(U20-LINEOUT1P-PadB5)") (class "Default")
      (node (ref "U20") (pin "B5") (pinfunction "LINEOUT1P_B5") (pintype "passive"))
    )
    (net (code "76") (name "unconnected-(U20-LINEOUT2N-PadC4)") (class "Default")
      (node (ref "U20") (pin "C4") (pinfunction "LINEOUT2N_C4") (pintype "passive"))
    )
    (net (code "77") (name "unconnected-(U20-LINEOUT2P-PadB4)") (class "Default")
      (node (ref "U20") (pin "B4") (pinfunction "LINEOUT2P_B4") (pintype "passive"))
    )
    (net (code "78") (name "unconnected-(U20-LINEOUTFB-PadA6)") (class "Default")
      (node (ref "U20") (pin "A6") (pinfunction "LINEOUTFB_A6") (pintype "passive"))
    )
    (net (code "79") (name "unconnected-(U20-SPKOUTLN-PadB1)") (class "Default")
      (node (ref "U20") (pin "B1") (pinfunction "SPKOUTLN_B1") (pintype "passive"))
    )
    (net (code "80") (name "unconnected-(U20-SPKOUTRN-PadC3)") (class "Default")
      (node (ref "U20") (pin "C3") (pinfunction "SPKOUTRN_C3") (pintype "passive"))
    )
  )
)
